# PPaddle.net
KiCad netlist of a schematic drawn in EAGLE
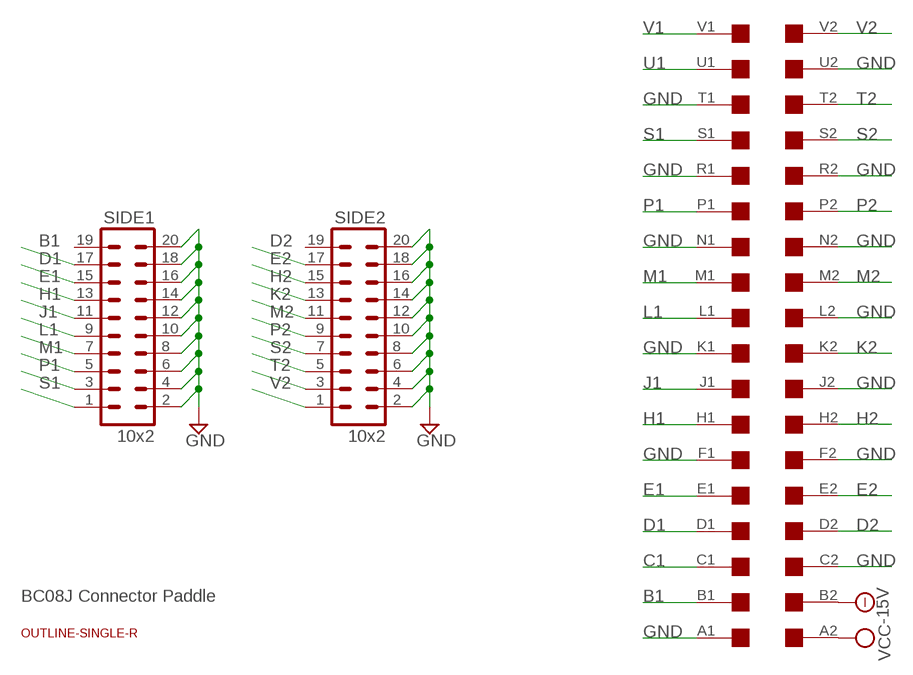
[diagram p0: schematic, sheet 1]

(export (version "E")
  (design (tool "Eeschema 10.0.6"))
  (components
    (comp (ref "SIDE1")
      (value "10x2")
      (footprint "eagle-import:20H")
      (libsource (lib "eagle-import") (part "20H"))
    )
    (comp (ref "SIDE2")
      (value "10x2")
      (footprint "eagle-import:20H")
      (libsource (lib "eagle-import") (part "20H"))
    )
    (comp (ref "U$1")
      (value "OUTLINE-SINGLE-R")
      (footprint "eagle-import:SINGLE-R")
      (libsource (lib "eagle-import") (part "OUTLINE-SINGLE-R"))
    )
    (comp (ref "U$2")
      (value "EDGE")
      (footprint "eagle-import:EDGE-CON2")
      (libsource (lib "eagle-import") (part "SINGLE"))
    )
  )
  (nets
    (net (code "1") (name "-15V") (class "Default")
      (node (ref "U$2") (pin "B2") (pinfunction "1_B2") (pintype "bidirectional"))
    )
    (net (code "2") (name "/B1") (class "Default")
      (node (ref "SIDE1") (pin "17") (pinfunction "17_17") (pintype "passive"))
      (node (ref "U$2") (pin "B1") (pinfunction "1_B1") (pintype "bidirectional"))
    )
    (net (code "3") (name "/C1") (class "Default")
      (node (ref "U$2") (pin "C1") (pinfunction "1_C1") (pintype "bidirectional"))
    )
    (net (code "4") (name "/D1") (class "Default")
      (node (ref "SIDE1") (pin "15") (pinfunction "15_15") (pintype "passive"))
      (node (ref "U$2") (pin "D1") (pinfunction "1_D1") (pintype "bidirectional"))
    )
    (net (code "5") (name "/D2") (class "Default")
      (node (ref "SIDE2") (pin "17") (pinfunction "17_17") (pintype "passive"))
      (node (ref "U$2") (pin "D2") (pinfunction "1_D2") (pintype "bidirectional"))
    )
    (net (code "6") (name "/E1") (class "Default")
      (node (ref "SIDE1") (pin "13") (pinfunction "13_13") (pintype "passive"))
      (node (ref "U$2") (pin "E1") (pinfunction "1_E1") (pintype "bidirectional"))
    )
    (net (code "7") (name "/E2") (class "Default")
      (node (ref "SIDE2") (pin "15") (pinfunction "15_15") (pintype "passive"))
      (node (ref "U$2") (pin "E2") (pinfunction "1_E2") (pintype "bidirectional"))
    )
    (net (code "8") (name "/H1") (class "Default")
      (node (ref "SIDE1") (pin "11") (pinfunction "11_11") (pintype "passive"))
      (node (ref "U$2") (pin "H1") (pinfunction "1_H1") (pintype "bidirectional"))
    )
    (net (code "9") (name "/H2") (class "Default")
      (node (ref "SIDE2") (pin "13") (pinfunction "13_13") (pintype "passive"))
      (node (ref "U$2") (pin "H2") (pinfunction "1_H2") (pintype "bidirectional"))
    )
    (net (code "10") (name "/J1") (class "Default")
      (node (ref "SIDE1") (pin "9") (pinfunction "9_9") (pintype "passive"))
      (node (ref "U$2") (pin "J1") (pinfunction "1_J1") (pintype "bidirectional"))
    )
    (net (code "11") (name "/K2") (class "Default")
      (node (ref "SIDE2") (pin "11") (pinfunction "11_11") (pintype "passive"))
      (node (ref "U$2") (pin "K2") (pinfunction "1_K2") (pintype "bidirectional"))
    )
    (net (code "12") (name "/L1") (class "Default")
      (node (ref "SIDE1") (pin "7") (pinfunction "7_7") (pintype "passive"))
      (node (ref "U$2") (pin "L1") (pinfunction "1_L1") (pintype "bidirectional"))
    )
    (net (code "13") (name "/M1") (class "Default")
      (node (ref "SIDE1") (pin "5") (pinfunction "5_5") (pintype "passive"))
      (node (ref "U$2") (pin "M1") (pinfunction "1_M1") (pintype "bidirectional"))
    )
    (net (code "14") (name "/M2") (class "Default")
      (node (ref "SIDE2") (pin "9") (pinfunction "9_9") (pintype "passive"))
      (node (ref "U$2") (pin "M2") (pinfunction "1_M2") (pintype "bidirectional"))
    )
    (net (code "15") (name "/P1") (class "Default")
      (node (ref "SIDE1") (pin "3") (pinfunction "3_3") (pintype "passive"))
      (node (ref "U$2") (pin "P1") (pinfunction "1_P1") (pintype "bidirectional"))
    )
    (net (code "16") (name "/P2") (class "Default")
      (node (ref "SIDE2") (pin "7") (pinfunction "7_7") (pintype "passive"))
      (node (ref "U$2") (pin "P2") (pinfunction "1_P2") (pintype "bidirectional"))
    )
    (net (code "17") (name "/S1") (class "Default")
      (node (ref "SIDE1") (pin "1") (pinfunction "1_1") (pintype "passive"))
      (node (ref "U$2") (pin "S1") (pinfunction "1_S1") (pintype "bidirectional"))
    )
    (net (code "18") (name "/S2") (class "Default")
      (node (ref "SIDE2") (pin "5") (pinfunction "5_5") (pintype "passive"))
      (node (ref "U$2") (pin "S2") (pinfunction "1_S2") (pintype "bidirectional"))
    )
    (net (code "19") (name "/T2") (class "Default")
      (node (ref "SIDE2") (pin "3") (pinfunction "3_3") (pintype "passive"))
      (node (ref "U$2") (pin "T2") (pinfunction "1_T2") (pintype "bidirectional"))
    )
    (net (code "20") (name "/U1") (class "Default")
      (node (ref "U$2") (pin "U1") (pinfunction "1_U1") (pintype "bidirectional"))
    )
    (net (code "21") (name "/V1") (class "Default")
      (node (ref "U$2") (pin "V1") (pinfunction "1_V1") (pintype "bidirectional"))
    )
    (net (code "22") (name "/V2") (class "Default")
      (node (ref "SIDE2") (pin "1") (pinfunction "1_1") (pintype "passive"))
      (node (ref "U$2") (pin "V2") (pinfunction "1_V2") (pintype "bidirectional"))
    )
    (net (code "23") (name "GND") (class "Default")
      (node (ref "SIDE1") (pin "10") (pinfunction "10_10") (pintype "passive"))
      (node (ref "SIDE1") (pin "12") (pinfunction "12_12") (pintype "passive"))
      (node (ref "SIDE1") (pin "14") (pinfunction "14_14") (pintype "passive"))
      (node (ref "SIDE1") (pin "16") (pinfunction "16_16") (pintype "passive"))
      (node (ref "SIDE1") (pin "18") (pinfunction "18_18") (pintype "passive"))
      (node (ref "SIDE1") (pin "2") (pinfunction "2_2") (pintype "passive"))
      (node (ref "SIDE1") (pin "20") (pinfunction "20_20") (pintype "passive"))
      (node (ref "SIDE1") (pin "4") (pinfunction "4_4") (pintype "passive"))
      (node (ref "SIDE1") (pin "6") (pinfunction "6_6") (pintype "passive"))
      (node (ref "SIDE1") (pin "8") (pinfunction "8_8") (pintype "passive"))
      (node (ref "SIDE2") (pin "10") (pinfunction "10_10") (pintype "passive"))
      (node (ref "SIDE2") (pin "12") (pinfunction "12_12") (pintype "passive"))
      (node (ref "SIDE2") (pin "14") (pinfunction "14_14") (pintype "passive"))
      (node (ref "SIDE2") (pin "16") (pinfunction "16_16") (pintype "passive"))
      (node (ref "SIDE2") (pin "18") (pinfunction "18_18") (pintype "passive"))
      (node (ref "SIDE2") (pin "2") (pinfunction "2_2") (pintype "passive"))
      (node (ref "SIDE2") (pin "20") (pinfunction "20_20") (pintype "passive"))
      (node (ref "SIDE2") (pin "4") (pinfunction "4_4") (pintype "passive"))
      (node (ref "SIDE2") (pin "6") (pinfunction "6_6") (pintype "passive"))
      (node (ref "SIDE2") (pin "8") (pinfunction "8_8") (pintype "passive"))
      (node (ref "U$2") (pin "A1") (pinfunction "1_A1") (pintype "bidirectional"))
      (node (ref "U$2") (pin "C2") (pinfunction "1_C2") (pintype "bidirectional"))
      (node (ref "U$2") (pin "F1") (pinfunction "1_F1") (pintype "bidirectional"))
      (node (ref "U$2") (pin "F2") (pinfunction "1_F2") (pintype "bidirectional"))
      (node (ref "U$2") (pin "J2") (pinfunction "1_J2") (pintype "bidirectional"))
      (node (ref "U$2") (pin "K1") (pinfunction "1_K1") (pintype "bidirectional"))
      (node (ref "U$2") (pin "L2") (pinfunction "1_L2") (pintype "bidirectional"))
      (node (ref "U$2") (pin "N1") (pinfunction "1_N1") (pintype "bidirectional"))
      (node (ref "U$2") (pin "N2") (pinfunction "1_N2") (pintype "bidirectional"))
      (node (ref "U$2") (pin "R1") (pinfunction "1_R1") (pintype "bidirectional"))
      (node (ref "U$2") (pin "R2") (pinfunction "1_R2") (pintype "bidirectional"))
      (node (ref "U$2") (pin "T1") (pinfunction "1_T1") (pintype "bidirectional"))
      (node (ref "U$2") (pin "U2") (pinfunction "1_U2") (pintype "bidirectional"))
    )
    (net (code "24") (name "VCC") (class "Default")
      (node (ref "U$2") (pin "A2") (pinfunction "1_A2") (pintype "bidirectional"))
    )
    (net (code "25") (name "unconnected-(SIDE1-Pad19)") (class "Default")
      (node (ref "SIDE1") (pin "19") (pinfunction "19_19") (pintype "passive"))
    )
    (net (code "26") (name "unconnected-(SIDE2-Pad19)") (class "Default")
      (node (ref "SIDE2") (pin "19") (pinfunction "19_19") (pintype "passive"))
    )
  )
)
